# DisplayVolanteVE.net
KiCad netlist of a schematic drawn in EAGLE
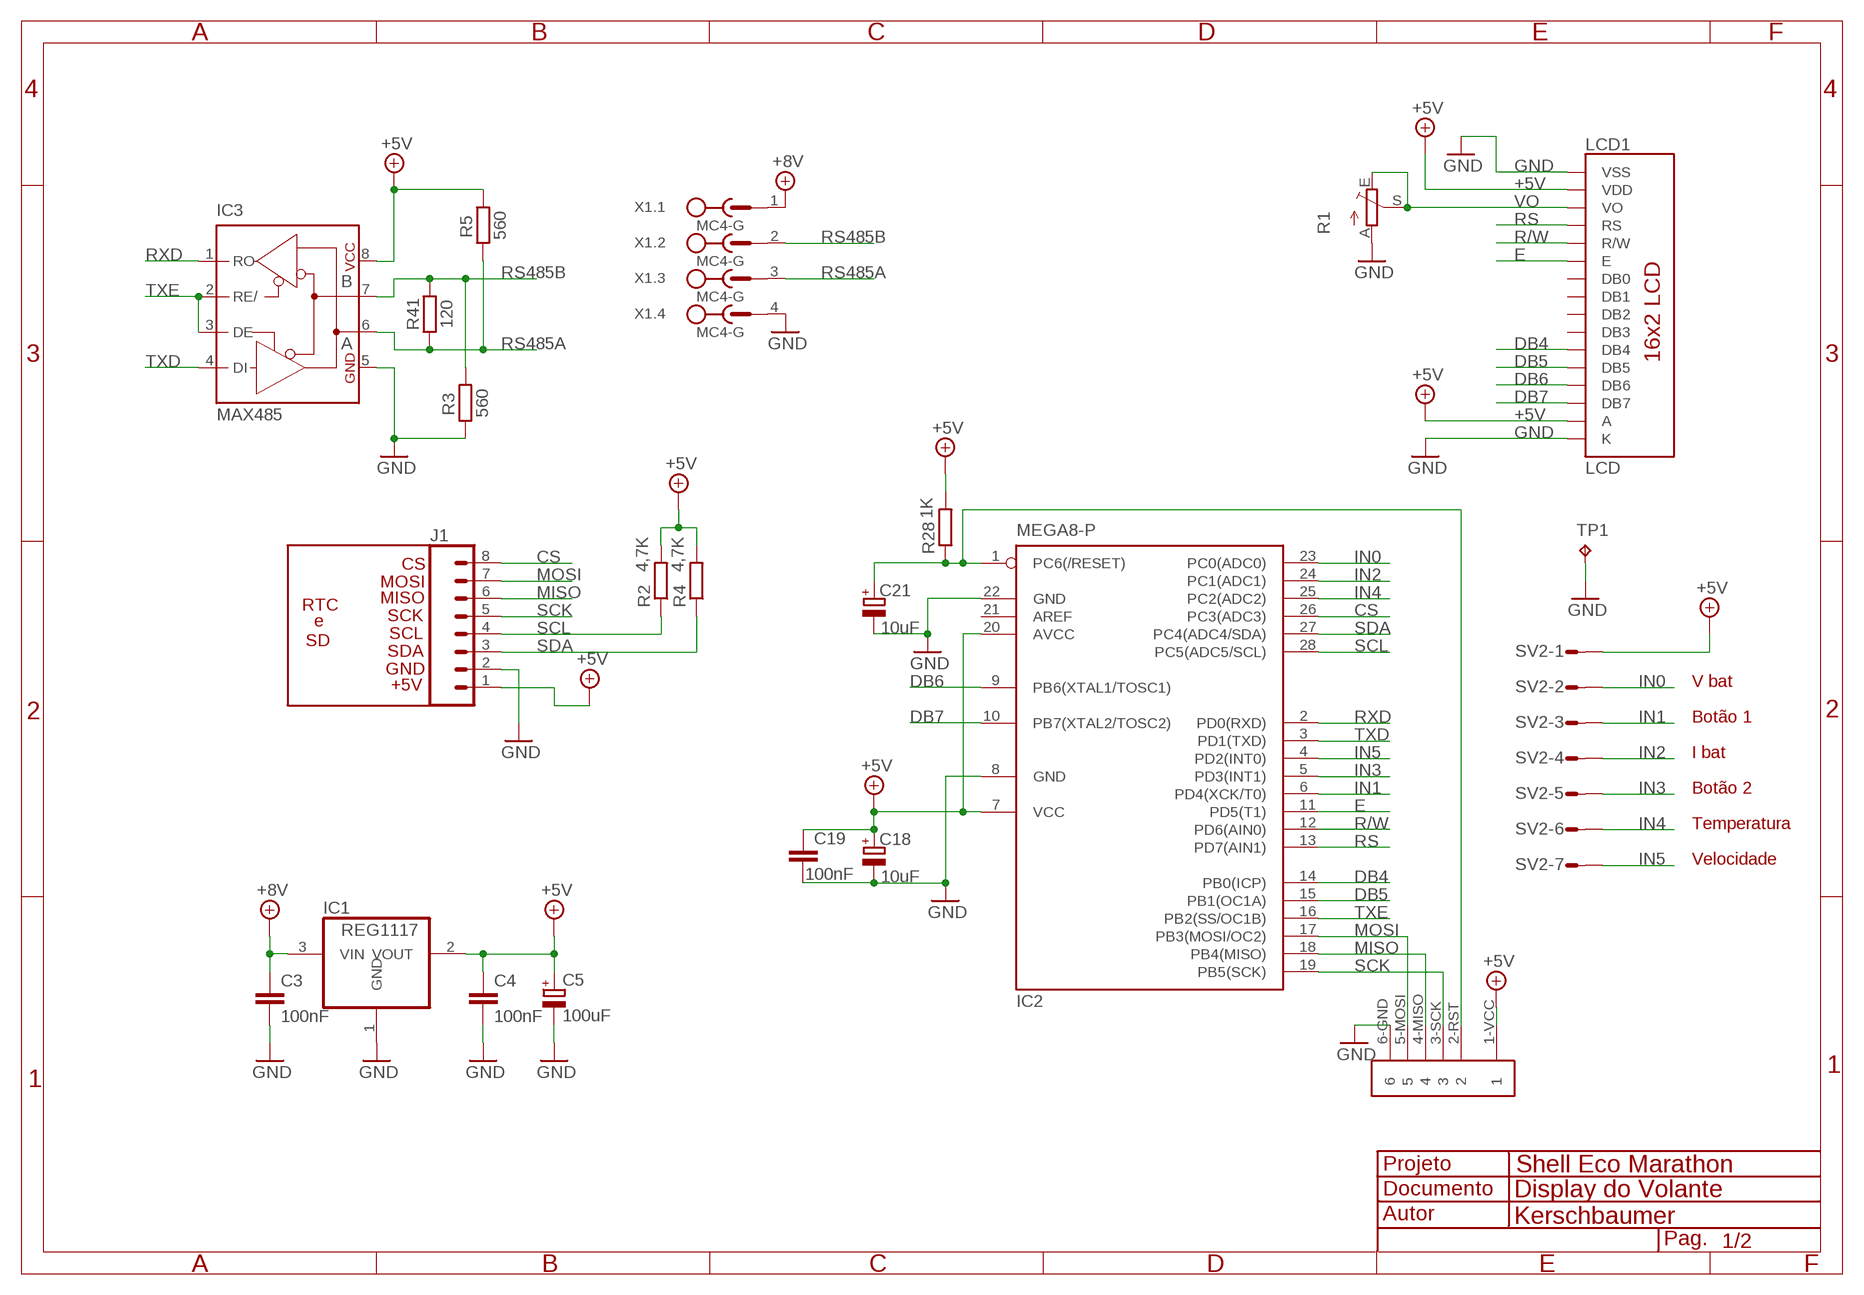
[diagram p0: schematic, sheet 1]
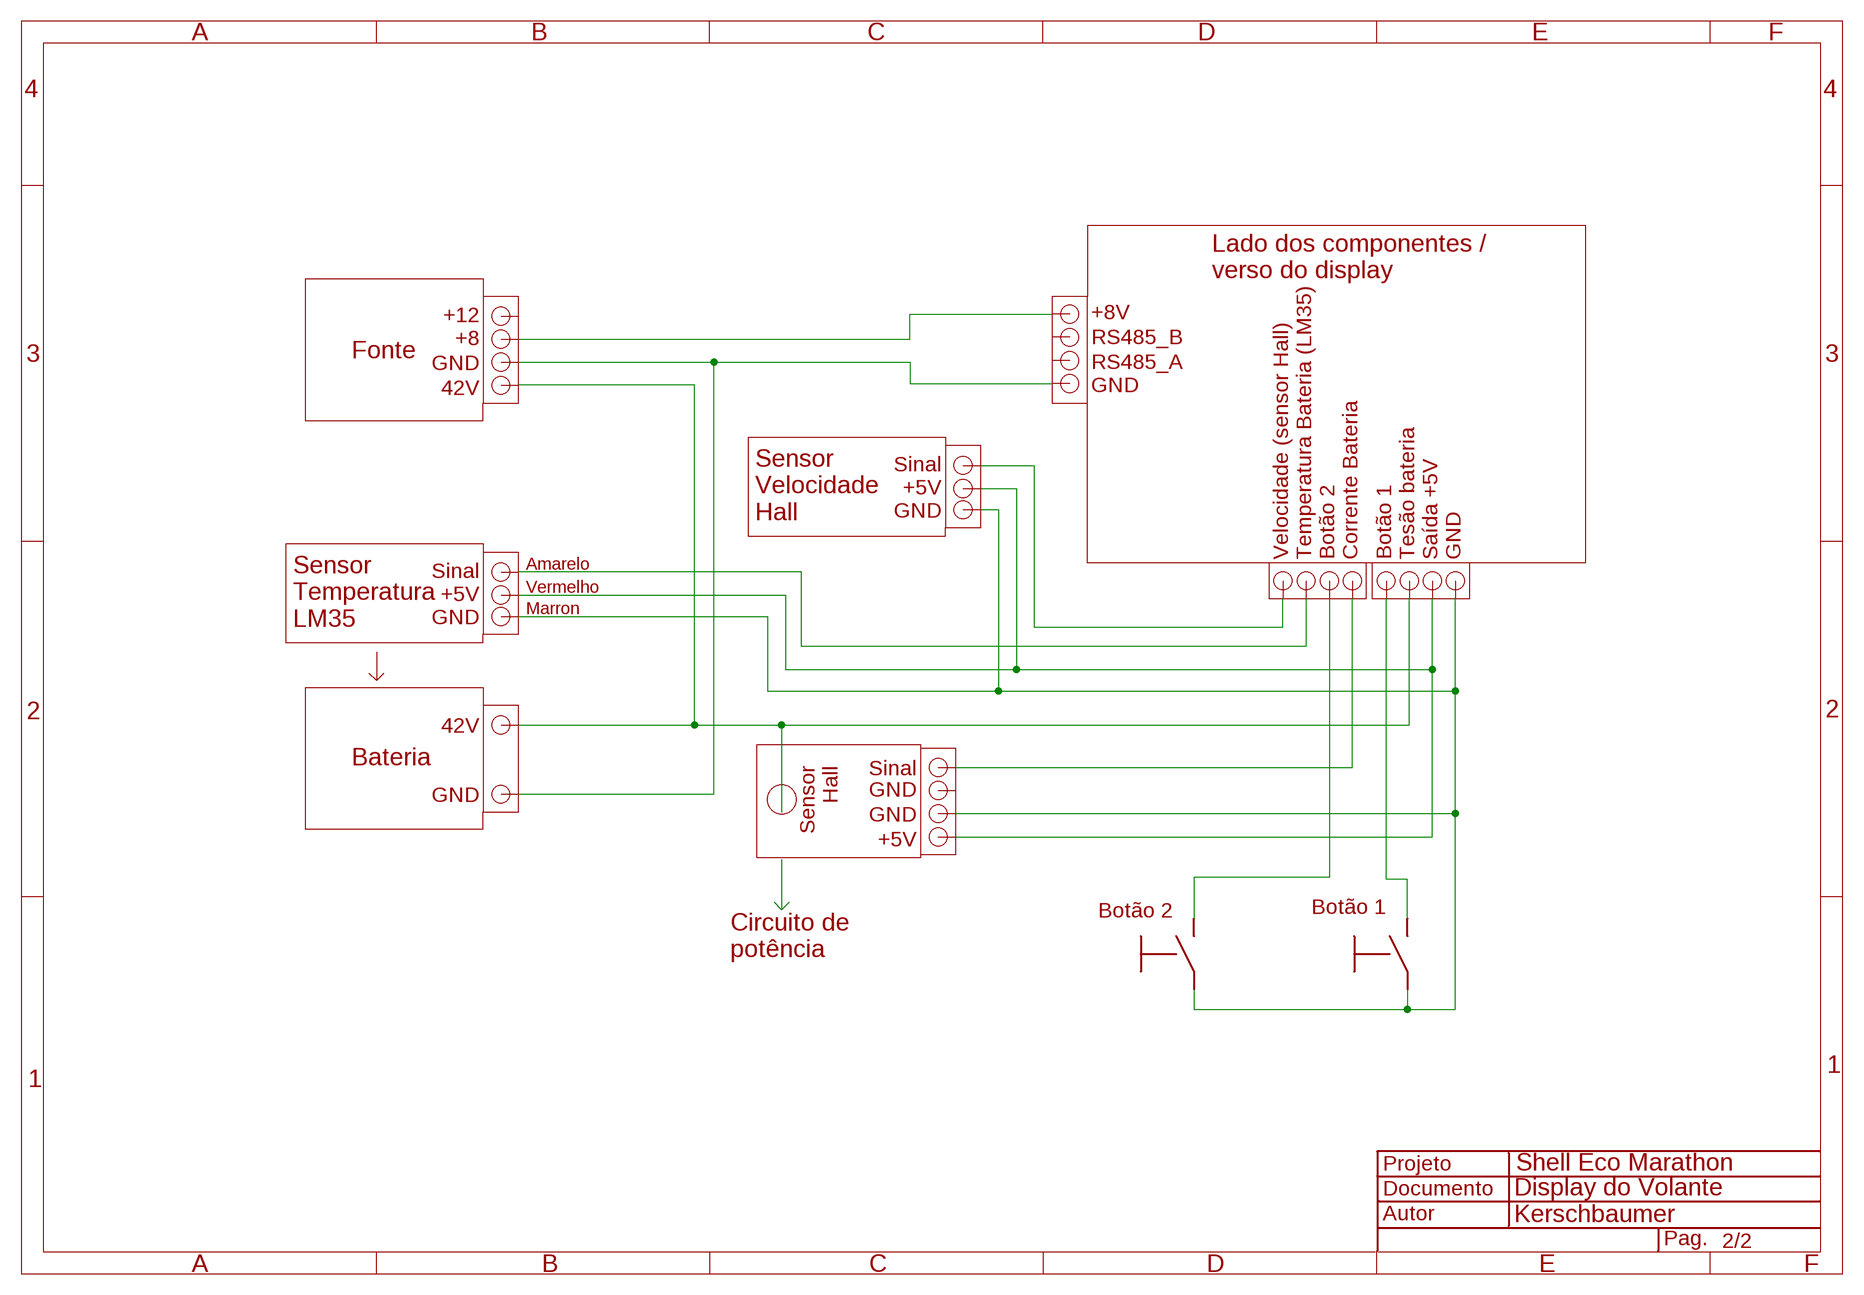
[diagram p1: schematic, sheet 2]

(export (version "E")
  (design (tool "Eeschema 10.0.6"))
  (components
    (comp (ref "C3")
      (value "100nF")
      (footprint "eagle-import:C050-025X075")
      (libsource (lib "eagle-import") (part "C-EU050-025X075"))
    )
    (comp (ref "C4")
      (value "100nF")
      (footprint "eagle-import:C050-025X075")
      (libsource (lib "eagle-import") (part "C-EU050-025X075"))
    )
    (comp (ref "C5")
      (value "100uF")
      (footprint "eagle-import:E2,5-6")
      (libsource (lib "eagle-import") (part "CPOL-EUE2.5-6"))
    )
    (comp (ref "C18")
      (value "10uF")
      (footprint "eagle-import:E2,5-6")
      (libsource (lib "eagle-import") (part "CPOL-EUE2.5-6"))
    )
    (comp (ref "C19")
      (value "100nF")
      (footprint "eagle-import:C050-025X075")
      (libsource (lib "eagle-import") (part "C-EU050-025X075"))
    )
    (comp (ref "C21")
      (value "10uF")
      (footprint "eagle-import:E2,5-6")
      (libsource (lib "eagle-import") (part "CPOL-EUE2.5-6"))
    )
    (comp (ref "IC1")
      (value "REG1117")
      (footprint "eagle-import:SOT223")
      (libsource (lib "eagle-import") (part "REG1117"))
    )
    (comp (ref "IC2")
      (value "MEGA8-P")
      (footprint "eagle-import:DIL28-3")
      (libsource (lib "eagle-import") (part "MEGA8-P"))
    )
    (comp (ref "IC3")
      (value "MAX485")
      (footprint "eagle-import:DIL08")
      (libsource (lib "eagle-import") (part "MAX485"))
    )
    (comp (ref "J1")
      (value "CONN_08NO_SILK_FEMALE_PTH")
      (footprint "eagle-import:1X08_NO_SILK")
      (libsource (lib "eagle-import") (part "CONN_08NO_SILK_FEMALE_PTH"))
    )
    (comp (ref "LCD1")
      (value "LCD")
      (footprint "eagle-import:LCD-16X2_NOHOLESNOSILK")
      (libsource (lib "eagle-import") (part "LCD-16X2NOHOLES"))
    )
    (comp (ref "P1")
      (value "SPI")
      (footprint "eagle-import:SPI")
      (libsource (lib "eagle-import") (part "SPI"))
    )
    (comp (ref "R1")
      (value "TRIM_EU-B64Y")
      (footprint "eagle-import:B64Y")
      (libsource (lib "eagle-import") (part "TRIM_EU-B64Y"))
    )
    (comp (ref "R2")
      (value "4,7K")
      (footprint "eagle-import:0207_7")
      (libsource (lib "eagle-import") (part "R-EU_0207/7"))
    )
    (comp (ref "R3")
      (value "560")
      (footprint "eagle-import:0207_7")
      (libsource (lib "eagle-import") (part "R-EU_0207/7"))
    )
    (comp (ref "R4")
      (value "4,7K")
      (footprint "eagle-import:0207_7")
      (libsource (lib "eagle-import") (part "R-EU_0207/7"))
    )
    (comp (ref "R5")
      (value "560")
      (footprint "eagle-import:0207_7")
      (libsource (lib "eagle-import") (part "R-EU_0207/7"))
    )
    (comp (ref "R28")
      (value "1K")
      (footprint "eagle-import:0207_7")
      (libsource (lib "eagle-import") (part "R-EU_0207/7"))
    )
    (comp (ref "R41")
      (value "120")
      (footprint "eagle-import:0207_7")
      (libsource (lib "eagle-import") (part "R-EU_0207/7"))
    )
    (comp (ref "SV2")
      (value "L07P")
      (footprint "eagle-import:L07P")
      (libsource (lib "eagle-import") (part "L07P"))
    )
    (comp (ref "TP1")
      (value "TPPAD1-13")
      (footprint "eagle-import:P1-13")
      (libsource (lib "eagle-import") (part "TPPAD1-13"))
    )
    (comp (ref "X1")
      (value "MC4-G")
      (footprint "eagle-import:MC4-G")
      (libsource (lib "eagle-import") (part "MC4-G"))
    )
  )
  (nets
    (net (code "1") (name "+5V") (class "Default")
      (node (ref "C18") (pin "+") (pinfunction "+_+") (pintype "passive"))
      (node (ref "C19") (pin "1") (pinfunction "1_1") (pintype "passive"))
      (node (ref "C4") (pin "1") (pinfunction "1_1") (pintype "passive"))
      (node (ref "C5") (pin "+") (pinfunction "+_+") (pintype "passive"))
      (node (ref "IC1") (pin "2") (pinfunction "VOUT_2") (pintype "output"))
      (node (ref "IC2") (pin "20") (pinfunction "AVCC_20") (pintype "power_in"))
      (node (ref "IC2") (pin "7") (pinfunction "VCC_7") (pintype "power_in"))
      (node (ref "IC3") (pin "8") (pinfunction "VCC_8") (pintype "power_in"))
      (node (ref "J1") (pin "1") (pinfunction "1_1") (pintype "passive"))
      (node (ref "LCD1") (pin "15") (pinfunction "A_15") (pintype "power_in"))
      (node (ref "LCD1") (pin "2") (pinfunction "VDD_2") (pintype "power_in"))
      (node (ref "P1") (pin "1-VCC") (pinfunction "1_1-VCC") (pintype "bidirectional"))
      (node (ref "R2") (pin "2") (pinfunction "2_2") (pintype "passive"))
      (node (ref "R28") (pin "2") (pinfunction "2_2") (pintype "passive"))
      (node (ref "R4") (pin "2") (pinfunction "2_2") (pintype "passive"))
      (node (ref "R5") (pin "2") (pinfunction "2_2") (pintype "passive"))
      (node (ref "SV2") (pin "1") (pinfunction "S_1") (pintype "passive"))
    )
    (net (code "2") (name "+8V") (class "Default")
      (node (ref "C3") (pin "1") (pinfunction "1_1") (pintype "passive"))
      (node (ref "IC1") (pin "3") (pinfunction "VIN_3") (pintype "input"))
      (node (ref "X1") (pin "1") (pinfunction "SK_1") (pintype "passive"))
    )
    (net (code "3") (name "CS") (class "Default")
      (node (ref "IC2") (pin "26") (pinfunction "PC3(ADC3)_26") (pintype "bidirectional"))
      (node (ref "J1") (pin "8") (pinfunction "8_8") (pintype "passive"))
    )
    (net (code "4") (name "DB4") (class "Default")
      (node (ref "IC2") (pin "14") (pinfunction "PB0(ICP)_14") (pintype "bidirectional"))
      (node (ref "LCD1") (pin "11") (pinfunction "DB4_11") (pintype "bidirectional"))
    )
    (net (code "5") (name "DB5") (class "Default")
      (node (ref "IC2") (pin "15") (pinfunction "PB1(OC1A)_15") (pintype "bidirectional"))
      (node (ref "LCD1") (pin "12") (pinfunction "DB5_12") (pintype "bidirectional"))
    )
    (net (code "6") (name "DB6") (class "Default")
      (node (ref "IC2") (pin "9") (pinfunction "PB6(XTAL1/TOSC1)_9") (pintype "bidirectional"))
      (node (ref "LCD1") (pin "13") (pinfunction "DB6_13") (pintype "bidirectional"))
    )
    (net (code "7") (name "DB7") (class "Default")
      (node (ref "IC2") (pin "10") (pinfunction "PB7(XTAL2/TOSC2)_10") (pintype "bidirectional"))
      (node (ref "LCD1") (pin "14") (pinfunction "DB7_14") (pintype "bidirectional"))
    )
    (net (code "8") (name "E") (class "Default")
      (node (ref "IC2") (pin "11") (pinfunction "PD5(T1)_11") (pintype "bidirectional"))
      (node (ref "LCD1") (pin "6") (pinfunction "E_6") (pintype "input"))
    )
    (net (code "9") (name "GND") (class "Default")
      (node (ref "C18") (pin "-") (pinfunction "-_-") (pintype "passive"))
      (node (ref "C19") (pin "2") (pinfunction "2_2") (pintype "passive"))
      (node (ref "C21") (pin "-") (pinfunction "-_-") (pintype "passive"))
      (node (ref "C3") (pin "2") (pinfunction "2_2") (pintype "passive"))
      (node (ref "C4") (pin "2") (pinfunction "2_2") (pintype "passive"))
      (node (ref "C5") (pin "-") (pinfunction "-_-") (pintype "passive"))
      (node (ref "IC1") (pin "1") (pinfunction "GND_1") (pintype "power_in"))
      (node (ref "IC2") (pin "22") (pinfunction "GND_22") (pintype "power_in"))
      (node (ref "IC2") (pin "8") (pinfunction "GND_8") (pintype "power_in"))
      (node (ref "IC3") (pin "5") (pinfunction "GND_5") (pintype "power_in"))
      (node (ref "J1") (pin "2") (pinfunction "2_2") (pintype "passive"))
      (node (ref "LCD1") (pin "1") (pinfunction "VSS_1") (pintype "power_in"))
      (node (ref "LCD1") (pin "16") (pinfunction "K_16") (pintype "power_in"))
      (node (ref "P1") (pin "6-GND") (pinfunction "6_6-GND") (pintype "bidirectional"))
      (node (ref "R1") (pin "A") (pinfunction "A_A") (pintype "passive"))
      (node (ref "R3") (pin "1") (pinfunction "1_1") (pintype "passive"))
      (node (ref "TP1") (pin "TP") (pinfunction "TP_TP") (pintype "input"))
      (node (ref "X1") (pin "4") (pinfunction "SK_4") (pintype "passive"))
    )
    (net (code "10") (name "IN0") (class "Default")
      (node (ref "IC2") (pin "23") (pinfunction "PC0(ADC0)_23") (pintype "bidirectional"))
      (node (ref "SV2") (pin "2") (pinfunction "S_2") (pintype "passive"))
    )
    (net (code "11") (name "IN1") (class "Default")
      (node (ref "IC2") (pin "6") (pinfunction "PD4(XCK/T0)_6") (pintype "bidirectional"))
      (node (ref "SV2") (pin "3") (pinfunction "S_3") (pintype "passive"))
    )
    (net (code "12") (name "IN2") (class "Default")
      (node (ref "IC2") (pin "24") (pinfunction "PC1(ADC1)_24") (pintype "bidirectional"))
      (node (ref "SV2") (pin "4") (pinfunction "S_4") (pintype "passive"))
    )
    (net (code "13") (name "IN3") (class "Default")
      (node (ref "IC2") (pin "5") (pinfunction "PD3(INT1)_5") (pintype "bidirectional"))
      (node (ref "SV2") (pin "5") (pinfunction "S_5") (pintype "passive"))
    )
    (net (code "14") (name "IN4") (class "Default")
      (node (ref "IC2") (pin "25") (pinfunction "PC2(ADC2)_25") (pintype "bidirectional"))
      (node (ref "SV2") (pin "6") (pinfunction "S_6") (pintype "passive"))
    )
    (net (code "15") (name "IN5") (class "Default")
      (node (ref "IC2") (pin "4") (pinfunction "PD2(INT0)_4") (pintype "bidirectional"))
      (node (ref "SV2") (pin "7") (pinfunction "S_7") (pintype "passive"))
    )
    (net (code "16") (name "MISO") (class "Default")
      (node (ref "IC2") (pin "18") (pinfunction "PB4(MISO)_18") (pintype "bidirectional"))
      (node (ref "J1") (pin "6") (pinfunction "6_6") (pintype "passive"))
      (node (ref "P1") (pin "4-MISO") (pinfunction "4_4-MISO") (pintype "bidirectional"))
    )
    (net (code "17") (name "MOSI") (class "Default")
      (node (ref "IC2") (pin "17") (pinfunction "PB3(MOSI/OC2)_17") (pintype "bidirectional"))
      (node (ref "J1") (pin "7") (pinfunction "7_7") (pintype "passive"))
      (node (ref "P1") (pin "5-MOSI") (pinfunction "5_5-MOSI") (pintype "bidirectional"))
    )
    (net (code "18") (name "Net-(IC2-PC6({slash}RESET))") (class "Default")
      (node (ref "C21") (pin "+") (pinfunction "+_+") (pintype "passive"))
      (node (ref "IC2") (pin "1") (pinfunction "PC6(/RESET)_1") (pintype "bidirectional"))
      (node (ref "P1") (pin "2-RST") (pinfunction "2_2-RST") (pintype "bidirectional"))
      (node (ref "R28") (pin "1") (pinfunction "1_1") (pintype "passive"))
    )
    (net (code "19") (name "RS") (class "Default")
      (node (ref "IC2") (pin "13") (pinfunction "PD7(AIN1)_13") (pintype "bidirectional"))
      (node (ref "LCD1") (pin "4") (pinfunction "RS_4") (pintype "input"))
    )
    (net (code "20") (name "RS485A") (class "Default")
      (node (ref "IC3") (pin "6") (pinfunction "A_6") (pintype "passive"))
      (node (ref "R41") (pin "1") (pinfunction "1_1") (pintype "passive"))
      (node (ref "R5") (pin "1") (pinfunction "1_1") (pintype "passive"))
      (node (ref "X1") (pin "3") (pinfunction "SK_3") (pintype "passive"))
    )
    (net (code "21") (name "RS485B") (class "Default")
      (node (ref "IC3") (pin "7") (pinfunction "B_7") (pintype "passive"))
      (node (ref "R3") (pin "2") (pinfunction "2_2") (pintype "passive"))
      (node (ref "R41") (pin "2") (pinfunction "2_2") (pintype "passive"))
      (node (ref "X1") (pin "2") (pinfunction "SK_2") (pintype "passive"))
    )
    (net (code "22") (name "RXD") (class "Default")
      (node (ref "IC2") (pin "2") (pinfunction "PD0(RXD)_2") (pintype "bidirectional"))
      (node (ref "IC3") (pin "1") (pinfunction "RO_1") (pintype "output"))
    )
    (net (code "23") (name "R{slash}W") (class "Default")
      (node (ref "IC2") (pin "12") (pinfunction "PD6(AIN0)_12") (pintype "bidirectional"))
      (node (ref "LCD1") (pin "5") (pinfunction "R/W_5") (pintype "input"))
    )
    (net (code "24") (name "SCK") (class "Default")
      (node (ref "IC2") (pin "19") (pinfunction "PB5(SCK)_19") (pintype "bidirectional"))
      (node (ref "J1") (pin "5") (pinfunction "5_5") (pintype "passive"))
      (node (ref "P1") (pin "3-SCK") (pinfunction "3_3-SCK") (pintype "bidirectional"))
    )
    (net (code "25") (name "SCL") (class "Default")
      (node (ref "IC2") (pin "28") (pinfunction "PC5(ADC5/SCL)_28") (pintype "bidirectional"))
      (node (ref "J1") (pin "4") (pinfunction "4_4") (pintype "passive"))
      (node (ref "R2") (pin "1") (pinfunction "1_1") (pintype "passive"))
    )
    (net (code "26") (name "SDA") (class "Default")
      (node (ref "IC2") (pin "27") (pinfunction "PC4(ADC4/SDA)_27") (pintype "bidirectional"))
      (node (ref "J1") (pin "3") (pinfunction "3_3") (pintype "passive"))
      (node (ref "R4") (pin "1") (pinfunction "1_1") (pintype "passive"))
    )
    (net (code "27") (name "TXD") (class "Default")
      (node (ref "IC2") (pin "3") (pinfunction "PD1(TXD)_3") (pintype "bidirectional"))
      (node (ref "IC3") (pin "4") (pinfunction "DI_4") (pintype "input"))
    )
    (net (code "28") (name "TXE") (class "Default")
      (node (ref "IC2") (pin "16") (pinfunction "PB2(SS/OC1B)_16") (pintype "bidirectional"))
      (node (ref "IC3") (pin "2") (pinfunction "RE/_2") (pintype "input"))
      (node (ref "IC3") (pin "3") (pinfunction "DE_3") (pintype "input"))
    )
    (net (code "29") (name "VO") (class "Default")
      (node (ref "LCD1") (pin "3") (pinfunction "VO_3") (pintype "bidirectional"))
      (node (ref "R1") (pin "E") (pinfunction "E_E") (pintype "passive"))
      (node (ref "R1") (pin "S") (pinfunction "S_S") (pintype "passive"))
    )
    (net (code "30") (name "unconnected-(IC2-AREF-Pad21)") (class "Default")
      (node (ref "IC2") (pin "21") (pinfunction "AREF_21") (pintype "passive"))
    )
    (net (code "31") (name "unconnected-(LCD1-DB0-Pad7)") (class "Default")
      (node (ref "LCD1") (pin "7") (pinfunction "DB0_7") (pintype "bidirectional"))
    )
    (net (code "32") (name "unconnected-(LCD1-DB1-Pad8)") (class "Default")
      (node (ref "LCD1") (pin "8") (pinfunction "DB1_8") (pintype "bidirectional"))
    )
    (net (code "33") (name "unconnected-(LCD1-DB2-Pad9)") (class "Default")
      (node (ref "LCD1") (pin "9") (pinfunction "DB2_9") (pintype "bidirectional"))
    )
    (net (code "34") (name "unconnected-(LCD1-DB3-Pad10)") (class "Default")
      (node (ref "LCD1") (pin "10") (pinfunction "DB3_10") (pintype "bidirectional"))
    )
  )
)
